# cktDiag.net
KiCad netlist of a schematic drawn in EAGLE
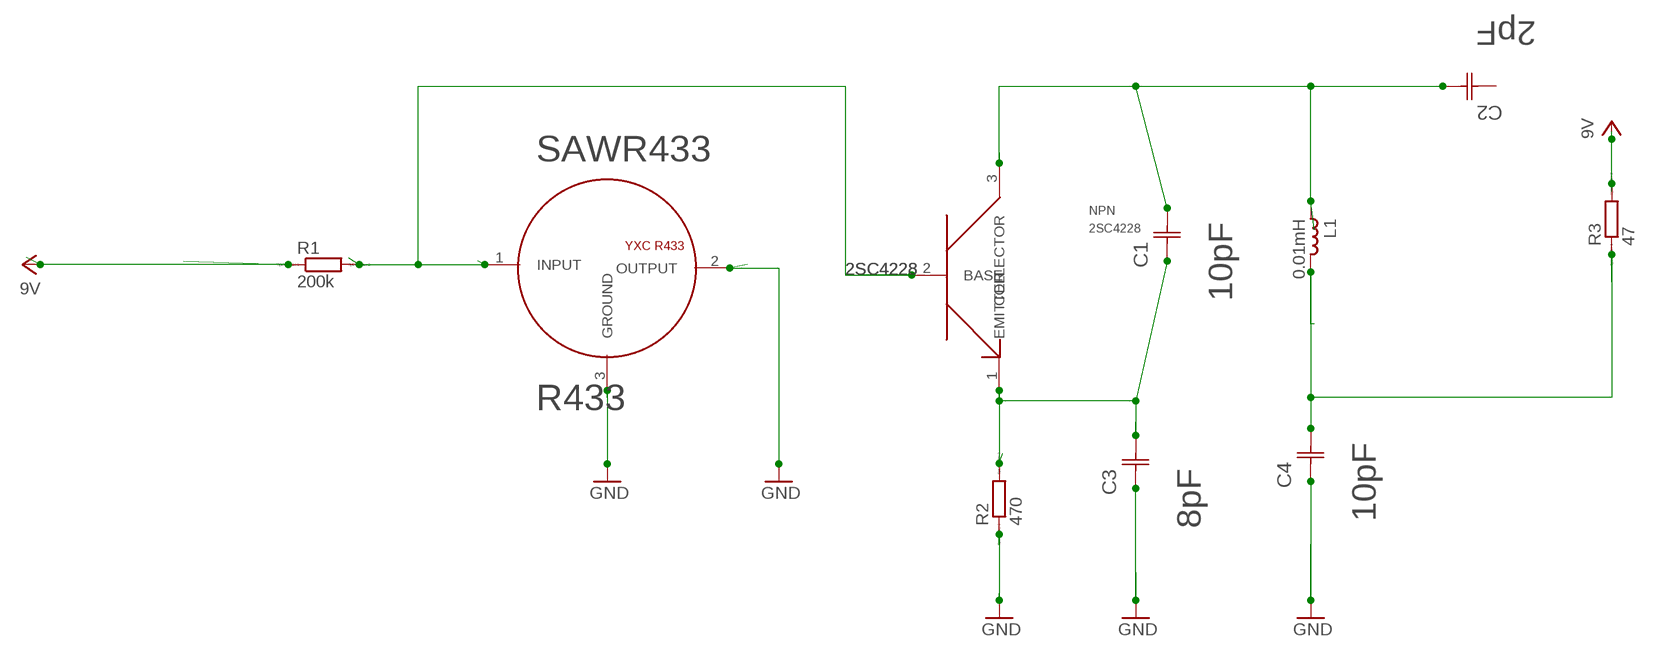
[diagram p0: schematic, sheet 1]

(export (version "E")
  (design (tool "Eeschema 10.0.6"))
  (components
    (comp (ref "C1")
      (value "10pF")
      (footprint "eagle-import:CAPC1608X85N")
      (fields (field (name "MPN") "GRM1885C1H102JA01D") (field (name "TOLERANCE") "±5%"))
      (libsource (lib "eagle-import") (part "GRM1885C1H102JA01D"))
    )
    (comp (ref "C2")
      (value "2pF")
      (footprint "eagle-import:CAPC1608X85N")
      (fields (field (name "MPN") "GRM1885C1H102JA01D") (field (name "TOLERANCE") "±5%"))
      (libsource (lib "eagle-import") (part "GRM1885C1H102JA01D"))
    )
    (comp (ref "C3")
      (value "8pF")
      (footprint "eagle-import:CAPC1608X85N")
      (fields (field (name "MPN") "GRM1885C1H102JA01D") (field (name "TOLERANCE") "±5%"))
      (libsource (lib "eagle-import") (part "GRM1885C1H102JA01D"))
    )
    (comp (ref "C4")
      (value "10pF")
      (footprint "eagle-import:CAPC1608X85N")
      (fields (field (name "MPN") "GRM1885C1H102JA01D") (field (name "TOLERANCE") "±5%"))
      (libsource (lib "eagle-import") (part "GRM1885C1H102JA01D"))
    )
    (comp (ref "L1")
      (value "0.01mH")
      (footprint "eagle-import:L0603")
      (libsource (lib "eagle-import") (part "L_0603"))
    )
    (comp (ref "NPN")
      (value "2SC4228")
      (footprint "eagle-import:2SC4228")
      (libsource (lib "eagle-import") (part "2SC4228"))
    )
    (comp (ref "R1")
      (value "200k")
      (footprint "eagle-import:R0603")
      (libsource (lib "eagle-import") (part "RR0603"))
    )
    (comp (ref "R2")
      (value "470")
      (footprint "eagle-import:R0603")
      (libsource (lib "eagle-import") (part "RR0603"))
    )
    (comp (ref "R3")
      (value "47")
      (footprint "eagle-import:R0603")
      (libsource (lib "eagle-import") (part "RR0603"))
    )
    (comp (ref "SAWR433")
      (value "R433")
      (footprint "eagle-import:RX33")
      (libsource (lib "eagle-import") (part "R433"))
    )
  )
  (nets
    (net (code "1") (name "/2SC4228") (class "Default")
      (node (ref "NPN") (pin "2") (pinfunction "BASE_2") (pintype "bidirectional"))
      (node (ref "R1") (pin "2") (pinfunction "2_2") (pintype "passive"))
      (node (ref "SAWR433") (pin "1") (pinfunction "INPUT_1") (pintype "bidirectional"))
    )
    (net (code "2") (name "9V") (class "Default")
      (node (ref "R1") (pin "1") (pinfunction "1_1") (pintype "passive"))
      (node (ref "R3") (pin "2") (pinfunction "2_2") (pintype "passive"))
    )
    (net (code "3") (name "GND") (class "Default")
      (node (ref "C3") (pin "1") (pinfunction "C1_1") (pintype "passive"))
      (node (ref "C4") (pin "1") (pinfunction "C1_1") (pintype "passive"))
      (node (ref "R2") (pin "1") (pinfunction "1_1") (pintype "passive"))
      (node (ref "SAWR433") (pin "2") (pinfunction "OUTPUT_2") (pintype "bidirectional"))
      (node (ref "SAWR433") (pin "3") (pinfunction "GROUND_3") (pintype "bidirectional"))
    )
    (net (code "4") (name "Net-(C1-C1)") (class "Default")
      (node (ref "C1") (pin "1") (pinfunction "C1_1") (pintype "passive"))
      (node (ref "C3") (pin "2") (pinfunction "C2_2") (pintype "passive"))
      (node (ref "NPN") (pin "1") (pinfunction "EMITTER_1") (pintype "bidirectional"))
      (node (ref "R2") (pin "2") (pinfunction "2_2") (pintype "passive"))
    )
    (net (code "5") (name "Net-(C1-C2)") (class "Default")
      (node (ref "C1") (pin "2") (pinfunction "C2_2") (pintype "passive"))
      (node (ref "C2") (pin "2") (pinfunction "C2_2") (pintype "passive"))
      (node (ref "L1") (pin "2") (pinfunction "2_2") (pintype "passive"))
      (node (ref "NPN") (pin "3") (pinfunction "COLLECTOR_3") (pintype "bidirectional"))
    )
    (net (code "6") (name "Net-(C4-C2)") (class "Default")
      (node (ref "C4") (pin "2") (pinfunction "C2_2") (pintype "passive"))
      (node (ref "L1") (pin "1") (pinfunction "1_1") (pintype "passive"))
      (node (ref "R3") (pin "1") (pinfunction "1_1") (pintype "passive"))
    )
    (net (code "7") (name "unconnected-(C2-C1-Pad1)") (class "Default")
      (node (ref "C2") (pin "1") (pinfunction "C1_1") (pintype "passive"))
    )
  )
)
